# main.net
KiCad netlist of a schematic drawn in Altium Designer
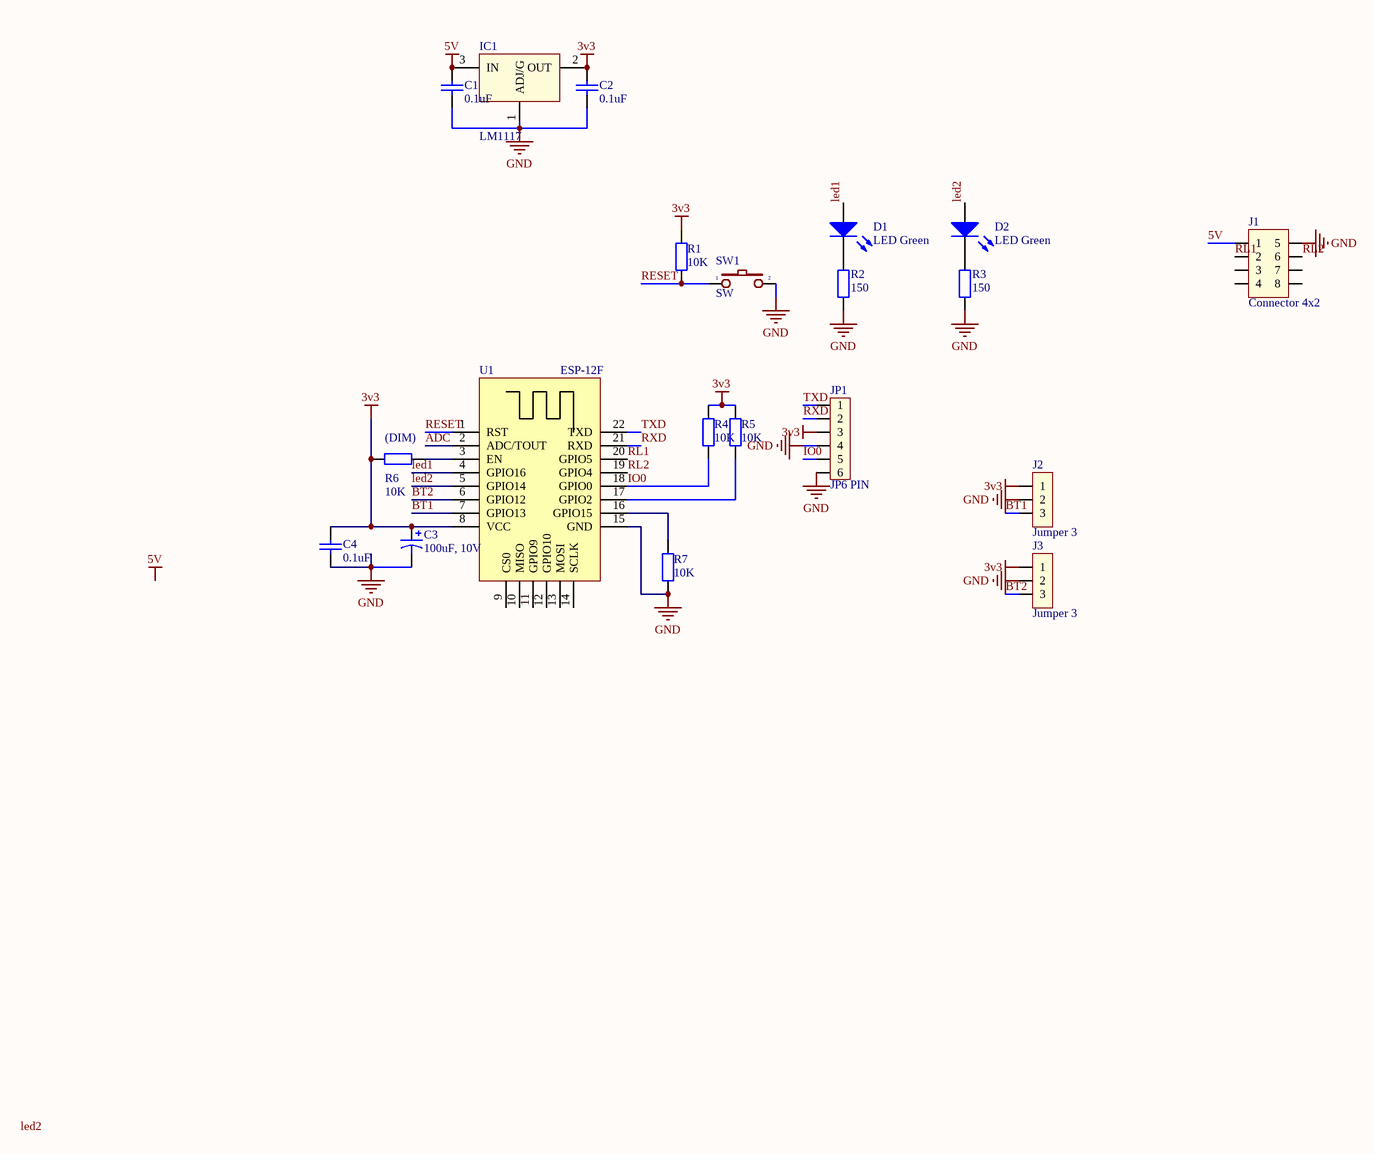
[diagram p0: main.schdoc]

(export (version "E")
  (design (tool "Eeschema 10.0.6"))
  (components
    (comp (ref "C1")
      (value "0.1uF")
      (footprint "C0603")
      (description "Murata General Purpose Ceramic Cap 0603 0.1uF 50V 10% X7R")
      (fields (field (name "Comment") "Ceramic Cap 0603 0.1uF 50V 10% X7R"))
      (libsource (lib "capacitor") (part "GRM188R71H104KA93"))
    )
    (comp (ref "C2")
      (value "0.1uF")
      (footprint "C0603")
      (description "Murata General Purpose Ceramic Cap 0603 0.1uF 50V 10% X7R")
      (fields (field (name "Comment") "Ceramic Cap 0603 0.1uF 50V 10% X7R"))
      (libsource (lib "capacitor") (part "GRM188R71H104KA93"))
    )
    (comp (ref "C3")
      (value "100uF, 10V")
      (footprint "C2917")
      (description "AVX Tantalum Cap 2917 100uF 10V 10% 100 mOhm")
      (fields (field (name "Comment") "Tantalum Cap 2917 100uF 10V 10% 100 mOhm"))
      (libsource (lib "capacitor") (part "TPSD107K010R0100"))
    )
    (comp (ref "C4")
      (value "0.1uF")
      (footprint "C0603")
      (description "Murata General Purpose Ceramic Cap 0603 0.1uF 50V 10% X7R")
      (fields (field (name "Comment") "Ceramic Cap 0603 0.1uF 50V 10% X7R"))
      (libsource (lib "capacitor") (part "GRM188R71H104KA93"))
    )
    (comp (ref "D1")
      (value "LED Green")
      (footprint "LED0603-G")
      (description "Lite-On LED Green 0603")
      (libsource (lib "diode") (part "LTST-C190KGKT"))
    )
    (comp (ref "D2")
      (value "LED Green")
      (footprint "LED0603-G")
      (description "Lite-On LED Green 0603")
      (libsource (lib "diode") (part "LTST-C190KGKT"))
    )
    (comp (ref "IC1")
      (value "LM1117")
      (footprint "SOT223-4N")
      (description "3v3")
      (libsource (lib "hanguyen") (part "LM1117"))
    )
    (comp (ref "J1") (value "Connector 4x2") (footprint "JP4x2") (libsource (lib "hanguyen") (part "JP4x2")))
    (comp (ref "J2") (value "Jumper 3") (footprint "JP3") (libsource (lib "hanguyen") (part "JP3")))
    (comp (ref "J3") (value "Jumper 3") (footprint "JP3") (libsource (lib "hanguyen") (part "JP3")))
    (comp (ref "JP1") (value "JP6 PIN") (footprint "JP6") (libsource (lib "hanguyen") (part "JP6")))
    (comp (ref "R1")
      (value "10K")
      (footprint "R0603")
      (description "Yageo RES 10K 5% 1/10W 0603")
      (fields (field (name "Comment") "RES 10K 5% 1/10W 0603"))
      (libsource (lib "resistor") (part "RC0603JR-0710KL"))
    )
    (comp (ref "R2")
      (value "150")
      (footprint "R0603")
      (description "Resistor SMD")
      (libsource (lib "hanguyen") (part "RM"))
    )
    (comp (ref "R3")
      (value "150")
      (footprint "R0603")
      (description "Resistor SMD")
      (libsource (lib "hanguyen") (part "RM"))
    )
    (comp (ref "R4")
      (value "10K")
      (footprint "R0603")
      (description "Yageo RES 10K 5% 1/10W 0603")
      (fields (field (name "Comment") "RES 10K 5% 1/10W 0603"))
      (libsource (lib "resistor") (part "RC0603JR-0710KL"))
    )
    (comp (ref "R5")
      (value "10K")
      (footprint "R0603")
      (description "Yageo RES 10K 5% 1/10W 0603")
      (fields (field (name "Comment") "RES 10K 5% 1/10W 0603"))
      (libsource (lib "resistor") (part "RC0603JR-0710KL"))
    )
    (comp (ref "R6")
      (value "10K")
      (footprint "R0603")
      (description "Yageo RES 10K 5% 1/10W 0603")
      (fields (field (name "Comment") "RES 10K 5% 1/10W 0603"))
      (libsource (lib "") (part "RC0603JR-0710KL_2"))
    )
    (comp (ref "R7")
      (value "10K")
      (footprint "R0603")
      (description "Yageo RES 10K 5% 1/10W 0603")
      (fields (field (name "Comment") "RES 10K 5% 1/10W 0603"))
      (libsource (lib "") (part "RC0603JR-0710KL_1"))
    )
    (comp (ref "SW1")
      (value "SW")
      (footprint "SW1-SMD")
      (description "Switch button 2 pin")
      (libsource (lib "Thư Viện Altium FULL HD") (part "SW2"))
    )
    (comp (ref "U1")
      (value "ESP-12F")
      (footprint "ESP-12F")
      (description "ESP-12F WiFi Module")
      (libsource (lib "hanguyen") (part "ESP-12F"))
    )
  )
  (nets
    (net (code "1") (name "/ADC") (class "Default")
      (node (ref "U1") (pin "2") (pinfunction "ADC/TOUT_2") (pintype "passive"))
    )
    (net (code "2") (name "/BT1") (class "Default")
      (node (ref "J2") (pin "3") (pinfunction "3_3") (pintype "passive"))
      (node (ref "U1") (pin "7") (pinfunction "GPIO13_7") (pintype "passive"))
    )
    (net (code "3") (name "/BT2") (class "Default")
      (node (ref "J3") (pin "3") (pinfunction "3_3") (pintype "passive"))
      (node (ref "U1") (pin "6") (pinfunction "GPIO12_6") (pintype "passive"))
    )
    (net (code "4") (name "/IO0") (class "Default")
      (node (ref "JP1") (pin "5") (pinfunction "5_5") (pintype "passive"))
      (node (ref "R4") (pin "1") (pinfunction "1_1") (pintype "passive"))
      (node (ref "U1") (pin "18") (pinfunction "GPIO0_18") (pintype "passive"))
    )
    (net (code "5") (name "/RESET") (class "Default")
      (node (ref "R1") (pin "1") (pinfunction "1_1") (pintype "passive"))
      (node (ref "SW1") (pin "1") (pinfunction "1_1") (pintype "passive"))
      (node (ref "U1") (pin "1") (pinfunction "RST_1") (pintype "passive"))
    )
    (net (code "6") (name "/RL1") (class "Default")
      (node (ref "J1") (pin "2") (pinfunction "2_2") (pintype "passive"))
      (node (ref "U1") (pin "20") (pinfunction "GPIO5_20") (pintype "passive"))
    )
    (net (code "7") (name "/RL2") (class "Default")
      (node (ref "J1") (pin "6") (pinfunction "6_6") (pintype "passive"))
      (node (ref "U1") (pin "19") (pinfunction "GPIO4_19") (pintype "passive"))
    )
    (net (code "8") (name "/RXD") (class "Default")
      (node (ref "JP1") (pin "2") (pinfunction "2_2") (pintype "passive"))
      (node (ref "U1") (pin "21") (pinfunction "RXD_21") (pintype "passive"))
    )
    (net (code "9") (name "/TXD") (class "Default")
      (node (ref "JP1") (pin "1") (pinfunction "1_1") (pintype "passive"))
      (node (ref "U1") (pin "22") (pinfunction "TXD_22") (pintype "passive"))
    )
    (net (code "10") (name "/led1") (class "Default")
      (node (ref "D1") (pin "1") (pinfunction "A_1") (pintype "passive"))
      (node (ref "U1") (pin "4") (pinfunction "GPIO16_4") (pintype "passive"))
    )
    (net (code "11") (name "/led2") (class "Default")
      (node (ref "D2") (pin "1") (pinfunction "A_1") (pintype "passive"))
      (node (ref "U1") (pin "5") (pinfunction "GPIO14_5") (pintype "passive"))
    )
    (net (code "12") (name "3v3") (class "Default")
      (node (ref "C2") (pin "1") (pinfunction "1_1") (pintype "passive"))
      (node (ref "C3") (pin "1") (pinfunction "1_1") (pintype "passive"))
      (node (ref "C4") (pin "1") (pinfunction "1_1") (pintype "passive"))
      (node (ref "IC1") (pin "2") (pinfunction "OUT_2") (pintype "passive"))
      (node (ref "J2") (pin "1") (pinfunction "1_1") (pintype "passive"))
      (node (ref "J3") (pin "1") (pinfunction "1_1") (pintype "passive"))
      (node (ref "JP1") (pin "3") (pinfunction "3_3") (pintype "passive"))
      (node (ref "R1") (pin "2") (pinfunction "2_2") (pintype "passive"))
      (node (ref "R4") (pin "2") (pinfunction "2_2") (pintype "passive"))
      (node (ref "R5") (pin "2") (pinfunction "2_2") (pintype "passive"))
      (node (ref "R6") (pin "2") (pinfunction "2_2") (pintype "passive"))
      (node (ref "U1") (pin "8") (pinfunction "VCC_8") (pintype "passive"))
    )
    (net (code "13") (name "5V") (class "Default")
      (node (ref "C1") (pin "1") (pinfunction "1_1") (pintype "passive"))
      (node (ref "IC1") (pin "3") (pinfunction "IN_3") (pintype "passive"))
      (node (ref "J1") (pin "1") (pinfunction "1_1") (pintype "passive"))
    )
    (net (code "14") (name "GND") (class "Default")
      (node (ref "C1") (pin "2") (pinfunction "2_2") (pintype "passive"))
      (node (ref "C2") (pin "2") (pinfunction "2_2") (pintype "passive"))
      (node (ref "C3") (pin "2") (pinfunction "2_2") (pintype "passive"))
      (node (ref "C4") (pin "2") (pinfunction "2_2") (pintype "passive"))
      (node (ref "IC1") (pin "1") (pinfunction "ADJ/G_1") (pintype "passive"))
      (node (ref "J1") (pin "5") (pinfunction "5_5") (pintype "passive"))
      (node (ref "J2") (pin "2") (pinfunction "2_2") (pintype "passive"))
      (node (ref "J3") (pin "2") (pinfunction "2_2") (pintype "passive"))
      (node (ref "JP1") (pin "4") (pinfunction "4_4") (pintype "passive"))
      (node (ref "JP1") (pin "6") (pinfunction "6_6") (pintype "passive"))
      (node (ref "R2") (pin "2") (pinfunction "2_2") (pintype "passive"))
      (node (ref "R3") (pin "2") (pinfunction "2_2") (pintype "passive"))
      (node (ref "R7") (pin "2") (pinfunction "2_2") (pintype "passive"))
      (node (ref "SW1") (pin "2") (pinfunction "2_2") (pintype "passive"))
      (node (ref "U1") (pin "15") (pinfunction "GND_15") (pintype "passive"))
    )
    (net (code "15") (name "Net-(D1-K)") (class "Default")
      (node (ref "D1") (pin "2") (pinfunction "K_2") (pintype "passive"))
      (node (ref "R2") (pin "1") (pinfunction "1_1") (pintype "passive"))
    )
    (net (code "16") (name "Net-(D2-K)") (class "Default")
      (node (ref "D2") (pin "2") (pinfunction "K_2") (pintype "passive"))
      (node (ref "R3") (pin "1") (pinfunction "1_1") (pintype "passive"))
    )
    (net (code "17") (name "Net-(U1-EN)") (class "Default")
      (node (ref "R6") (pin "1") (pinfunction "1_1") (pintype "passive"))
      (node (ref "U1") (pin "3") (pinfunction "EN_3") (pintype "passive"))
    )
    (net (code "18") (name "Net-(U1-GPIO2)") (class "Default")
      (node (ref "R5") (pin "1") (pinfunction "1_1") (pintype "passive"))
      (node (ref "U1") (pin "17") (pinfunction "GPIO2_17") (pintype "passive"))
    )
    (net (code "19") (name "Net-(U1-GPIO15)") (class "Default")
      (node (ref "R7") (pin "1") (pinfunction "1_1") (pintype "passive"))
      (node (ref "U1") (pin "16") (pinfunction "GPIO15_16") (pintype "passive"))
    )
    (net (code "20") (name "unconnected-(J1-Pad3)") (class "Default")
      (node (ref "J1") (pin "3") (pinfunction "3_3") (pintype "passive"))
    )
    (net (code "21") (name "unconnected-(J1-Pad4)") (class "Default")
      (node (ref "J1") (pin "4") (pinfunction "4_4") (pintype "passive"))
    )
    (net (code "22") (name "unconnected-(J1-Pad7)") (class "Default")
      (node (ref "J1") (pin "7") (pinfunction "7_7") (pintype "passive"))
    )
    (net (code "23") (name "unconnected-(J1-Pad8)") (class "Default")
      (node (ref "J1") (pin "8") (pinfunction "8_8") (pintype "passive"))
    )
    (net (code "24") (name "unconnected-(U1-CS0-Pad9)") (class "Default")
      (node (ref "U1") (pin "9") (pinfunction "CS0_9") (pintype "passive"))
    )
    (net (code "25") (name "unconnected-(U1-GPIO9-Pad11)") (class "Default")
      (node (ref "U1") (pin "11") (pinfunction "GPIO9_11") (pintype "passive"))
    )
    (net (code "26") (name "unconnected-(U1-GPIO10-Pad12)") (class "Default")
      (node (ref "U1") (pin "12") (pinfunction "GPIO10_12") (pintype "passive"))
    )
    (net (code "27") (name "unconnected-(U1-MISO-Pad10)") (class "Default")
      (node (ref "U1") (pin "10") (pinfunction "MISO_10") (pintype "passive"))
    )
    (net (code "28") (name "unconnected-(U1-MOSI-Pad13)") (class "Default")
      (node (ref "U1") (pin "13") (pinfunction "MOSI_13") (pintype "passive"))
    )
    (net (code "29") (name "unconnected-(U1-SCLK-Pad14)") (class "Default")
      (node (ref "U1") (pin "14") (pinfunction "SCLK_14") (pintype "passive"))
    )
  )
)
